# blink1mk2_v2c5.net
KiCad netlist of a schematic drawn in EAGLE
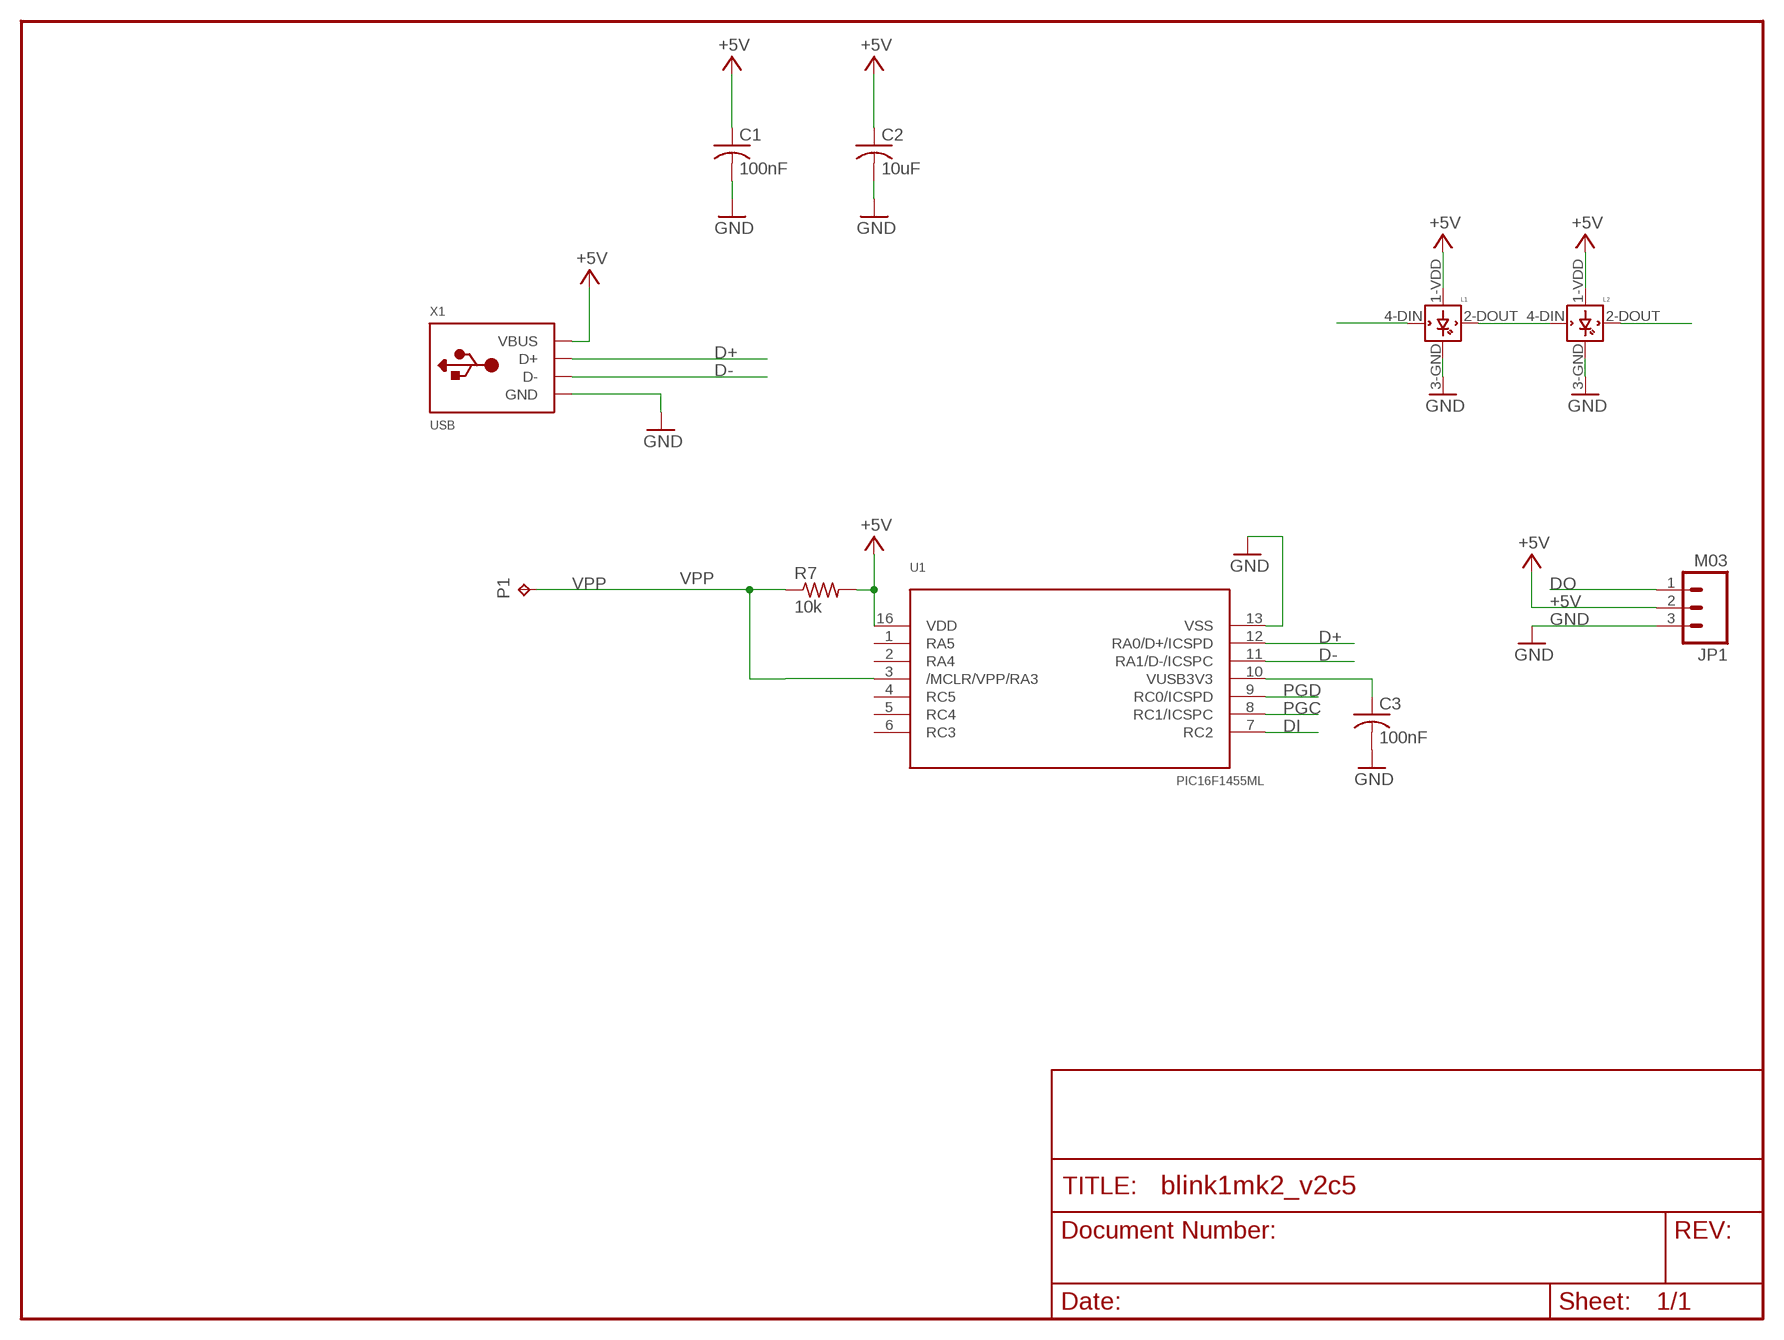
[diagram p0: schematic, sheet 1]

(export (version "E")
  (design (tool "Eeschema 10.0.6"))
  (components
    (comp (ref "C1")
      (value "100nF")
      (footprint "eagle-import:C0603")
      (libsource (lib "eagle-import") (part "C-USC0603"))
    )
    (comp (ref "C2")
      (value "10uF")
      (footprint "eagle-import:C0603")
      (libsource (lib "eagle-import") (part "C-USC0603"))
    )
    (comp (ref "C3")
      (value "100nF")
      (footprint "eagle-import:C0603")
      (libsource (lib "eagle-import") (part "C-USC0603"))
    )
    (comp (ref "JP1")
      (value "M03")
      (footprint "eagle-import:1X03-1.27MM")
      (libsource (lib "eagle-import") (part "M03"))
    )
    (comp (ref "L1")
      (value "WS2812B")
      (footprint "eagle-import:WS2812B")
      (libsource (lib "eagle-import") (part "WS2812B"))
    )
    (comp (ref "L2")
      (value "WS2812B")
      (footprint "eagle-import:WS2812B")
      (libsource (lib "eagle-import") (part "WS2812B"))
    )
    (comp (ref "P1")
      (value "TPTP11SQ")
      (footprint "eagle-import:TP11SQ")
      (libsource (lib "eagle-import") (part "TPTP11SQ"))
    )
    (comp (ref "R7")
      (value "10k")
      (footprint "eagle-import:R0603")
      (libsource (lib "eagle-import") (part "R-US_R0603"))
    )
    (comp (ref "U1")
      (value "PIC16F1455ML")
      (footprint "eagle-import:QFN16_4X4")
      (libsource (lib "eagle-import") (part "PIC16F1455ML"))
    )
    (comp (ref "X1")
      (value "USB")
      (footprint "eagle-import:MOLEX-48037-1000")
      (libsource (lib "eagle-import") (part "USB"))
    )
  )
  (nets
    (net (code "1") (name "+5V") (class "Default")
      (node (ref "C1") (pin "1") (pinfunction "1_1") (pintype "passive"))
      (node (ref "C2") (pin "1") (pinfunction "1_1") (pintype "passive"))
      (node (ref "JP1") (pin "2") (pinfunction "2_2") (pintype "passive"))
      (node (ref "L1") (pin "1-VDD") (pinfunction "VDD_1-VDD") (pintype "bidirectional"))
      (node (ref "L2") (pin "1-VDD") (pinfunction "VDD_1-VDD") (pintype "bidirectional"))
      (node (ref "R7") (pin "2") (pinfunction "2_2") (pintype "passive"))
      (node (ref "U1") (pin "16") (pinfunction "VDD_16") (pintype "bidirectional"))
      (node (ref "X1") (pin "1") (pinfunction "VBUS_1") (pintype "power_in"))
    )
    (net (code "2") (name "/D+") (class "Default")
      (node (ref "U1") (pin "12") (pinfunction "RA0/D+/ICSPD_12") (pintype "bidirectional"))
      (node (ref "X1") (pin "3") (pinfunction "D+_3") (pintype "bidirectional"))
    )
    (net (code "3") (name "/D-") (class "Default")
      (node (ref "U1") (pin "11") (pinfunction "RA1/D-/ICSPC_11") (pintype "bidirectional"))
      (node (ref "X1") (pin "2") (pinfunction "D-_2") (pintype "bidirectional"))
    )
    (net (code "4") (name "/DI") (class "Default")
      (node (ref "L1") (pin "4-DIN") (pinfunction "DIN_4-DIN") (pintype "input"))
      (node (ref "U1") (pin "7") (pinfunction "RC2_7") (pintype "bidirectional"))
    )
    (net (code "5") (name "/DO") (class "Default")
      (node (ref "JP1") (pin "1") (pinfunction "1_1") (pintype "passive"))
      (node (ref "L2") (pin "2-DOUT") (pinfunction "DOUT_2-DOUT") (pintype "output"))
    )
    (net (code "6") (name "/PGC") (class "Default")
      (node (ref "U1") (pin "8") (pinfunction "RC1/ICSPC_8") (pintype "bidirectional"))
    )
    (net (code "7") (name "/PGD") (class "Default")
      (node (ref "U1") (pin "9") (pinfunction "RC0/ICSPD_9") (pintype "bidirectional"))
    )
    (net (code "8") (name "/VPP") (class "Default")
      (node (ref "P1") (pin "TP") (pinfunction "TP_TP") (pintype "input"))
      (node (ref "R7") (pin "1") (pinfunction "1_1") (pintype "passive"))
      (node (ref "U1") (pin "3") (pinfunction "/MCLR/VPP/RA3_3") (pintype "bidirectional"))
    )
    (net (code "9") (name "GND") (class "Default")
      (node (ref "C1") (pin "2") (pinfunction "2_2") (pintype "passive"))
      (node (ref "C2") (pin "2") (pinfunction "2_2") (pintype "passive"))
      (node (ref "C3") (pin "2") (pinfunction "2_2") (pintype "passive"))
      (node (ref "JP1") (pin "3") (pinfunction "3_3") (pintype "passive"))
      (node (ref "L1") (pin "3-GND") (pinfunction "GND_3-GND") (pintype "bidirectional"))
      (node (ref "L2") (pin "3-GND") (pinfunction "GND_3-GND") (pintype "bidirectional"))
      (node (ref "U1") (pin "13") (pinfunction "VSS_13") (pintype "bidirectional"))
      (node (ref "X1") (pin "4") (pinfunction "GND_4") (pintype "power_in"))
    )
    (net (code "10") (name "Net-(L1-DOUT)") (class "Default")
      (node (ref "L1") (pin "2-DOUT") (pinfunction "DOUT_2-DOUT") (pintype "output"))
      (node (ref "L2") (pin "4-DIN") (pinfunction "DIN_4-DIN") (pintype "input"))
    )
    (net (code "11") (name "Net-(U1-VUSB3V3)") (class "Default")
      (node (ref "C3") (pin "1") (pinfunction "1_1") (pintype "passive"))
      (node (ref "U1") (pin "10") (pinfunction "VUSB3V3_10") (pintype "bidirectional"))
    )
    (net (code "12") (name "unconnected-(U1-RA4-Pad2)") (class "Default")
      (node (ref "U1") (pin "2") (pinfunction "RA4_2") (pintype "bidirectional"))
    )
    (net (code "13") (name "unconnected-(U1-RA5-Pad1)") (class "Default")
      (node (ref "U1") (pin "1") (pinfunction "RA5_1") (pintype "bidirectional"))
    )
    (net (code "14") (name "unconnected-(U1-RC3-Pad6)") (class "Default")
      (node (ref "U1") (pin "6") (pinfunction "RC3_6") (pintype "bidirectional"))
    )
    (net (code "15") (name "unconnected-(U1-RC4-Pad5)") (class "Default")
      (node (ref "U1") (pin "5") (pinfunction "RC4_5") (pintype "bidirectional"))
    )
    (net (code "16") (name "unconnected-(U1-RC5-Pad4)") (class "Default")
      (node (ref "U1") (pin "4") (pinfunction "RC5_4") (pintype "bidirectional"))
    )
  )
)
